# Pico.net
KiCad netlist of a schematic drawn in Altium Designer
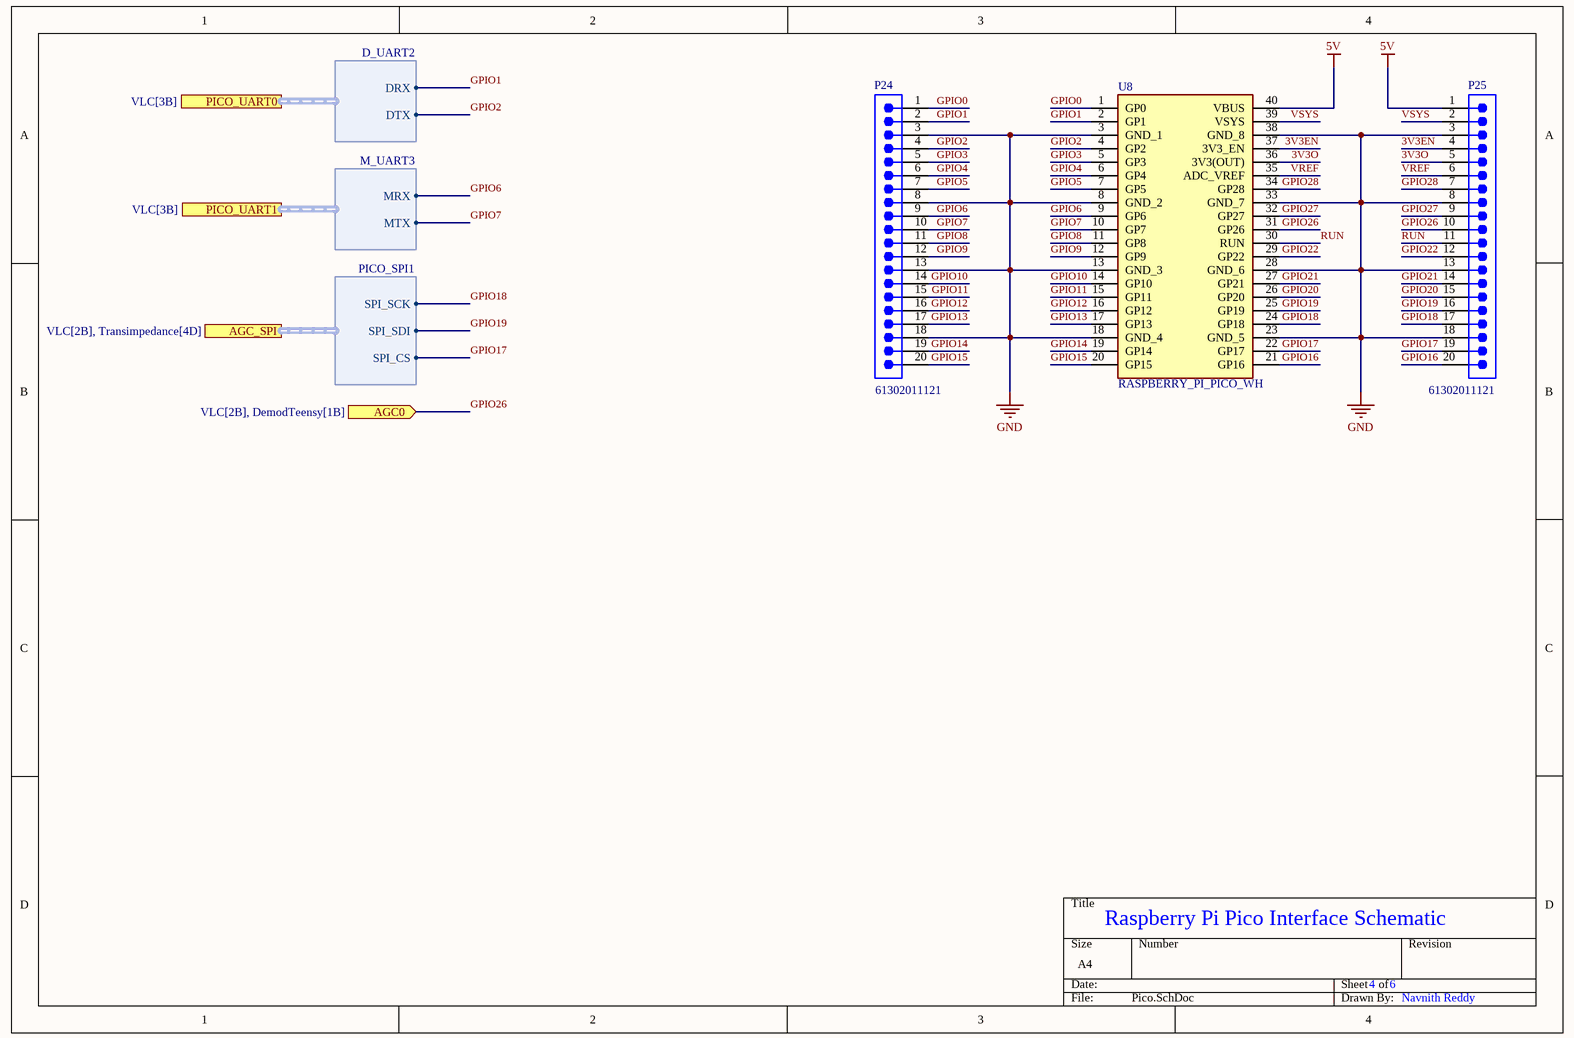
[diagram p0: Pico.SchDoc]

(export (version "E")
  (design (tool "Eeschema 10.0.6"))
  (components
    (comp (ref "P24")
      (value "61302011121")
      (footprint "61302011121")
      (libsource (lib "Altium Content Vault") (part "Header_Male_1R_20P"))
    )
    (comp (ref "P25")
      (value "61302011121")
      (footprint "61302011121")
      (libsource (lib "Altium Content Vault") (part "Header_Male_1R_20P"))
    )
    (comp (ref "U8")
      (value "RASPBERRY_PI_PICO_WH")
      (footprint "SamacSys:RASPBERRYPIPICOWH")
      (description "Undefined or Miscellaneous")
      (fields (field (name "MANUFACTURER_PART_NUMBER") "RASPBERRY PI PICO WH"))
      (libsource (lib "*") (part "RASPBERRY_PI_PICO_WH"))
    )
  )
  (nets
    (net (code "4") (name "/3V3EN") (class "Default")
      (node (ref "P25") (pin "4") (pinfunction "4_4") (pintype "passive"))
      (node (ref "U8") (pin "37") (pinfunction "3V3_EN_37") (pintype "passive"))
    )
    (net (code "5") (name "/3V3O") (class "Default")
      (node (ref "P25") (pin "5") (pinfunction "5_5") (pintype "passive"))
      (node (ref "U8") (pin "36") (pinfunction "3V3(OUT)_36") (pintype "passive"))
    )
    (net (code "6") (name "/GPIO0") (class "Default")
      (node (ref "P24") (pin "1") (pinfunction "1_1") (pintype "passive"))
      (node (ref "U8") (pin "1") (pinfunction "GP0_1") (pintype "passive"))
    )
    (net (code "7") (name "/GPIO1") (class "Default")
      (node (ref "P24") (pin "2") (pinfunction "2_2") (pintype "passive"))
      (node (ref "U8") (pin "2") (pinfunction "GP1_2") (pintype "passive"))
    )
    (net (code "8") (name "/GPIO2") (class "Default")
      (node (ref "P24") (pin "4") (pinfunction "4_4") (pintype "passive"))
      (node (ref "U8") (pin "4") (pinfunction "GP2_4") (pintype "passive"))
    )
    (net (code "9") (name "/GPIO3") (class "Default")
      (node (ref "P24") (pin "5") (pinfunction "5_5") (pintype "passive"))
      (node (ref "U8") (pin "5") (pinfunction "GP3_5") (pintype "passive"))
    )
    (net (code "10") (name "/GPIO4") (class "Default")
      (node (ref "P24") (pin "6") (pinfunction "6_6") (pintype "passive"))
      (node (ref "U8") (pin "6") (pinfunction "GP4_6") (pintype "passive"))
    )
    (net (code "11") (name "/GPIO5") (class "Default")
      (node (ref "P24") (pin "7") (pinfunction "7_7") (pintype "passive"))
      (node (ref "U8") (pin "7") (pinfunction "GP5_7") (pintype "passive"))
    )
    (net (code "12") (name "/GPIO6") (class "Default")
      (node (ref "P24") (pin "9") (pinfunction "9_9") (pintype "passive"))
      (node (ref "U8") (pin "9") (pinfunction "GP6_9") (pintype "passive"))
    )
    (net (code "13") (name "/GPIO7") (class "Default")
      (node (ref "P24") (pin "10") (pinfunction "10_10") (pintype "passive"))
      (node (ref "U8") (pin "10") (pinfunction "GP7_10") (pintype "passive"))
    )
    (net (code "14") (name "/GPIO8") (class "Default")
      (node (ref "P24") (pin "11") (pinfunction "11_11") (pintype "passive"))
      (node (ref "U8") (pin "11") (pinfunction "GP8_11") (pintype "passive"))
    )
    (net (code "15") (name "/GPIO9") (class "Default")
      (node (ref "P24") (pin "12") (pinfunction "12_12") (pintype "passive"))
      (node (ref "U8") (pin "12") (pinfunction "GP9_12") (pintype "passive"))
    )
    (net (code "16") (name "/GPIO10") (class "Default")
      (node (ref "P24") (pin "14") (pinfunction "14_14") (pintype "passive"))
      (node (ref "U8") (pin "14") (pinfunction "GP10_14") (pintype "passive"))
    )
    (net (code "17") (name "/GPIO11") (class "Default")
      (node (ref "P24") (pin "15") (pinfunction "15_15") (pintype "passive"))
      (node (ref "U8") (pin "15") (pinfunction "GP11_15") (pintype "passive"))
    )
    (net (code "18") (name "/GPIO12") (class "Default")
      (node (ref "P24") (pin "16") (pinfunction "16_16") (pintype "passive"))
      (node (ref "U8") (pin "16") (pinfunction "GP12_16") (pintype "passive"))
    )
    (net (code "19") (name "/GPIO13") (class "Default")
      (node (ref "P24") (pin "17") (pinfunction "17_17") (pintype "passive"))
      (node (ref "U8") (pin "17") (pinfunction "GP13_17") (pintype "passive"))
    )
    (net (code "20") (name "/GPIO14") (class "Default")
      (node (ref "P24") (pin "19") (pinfunction "19_19") (pintype "passive"))
      (node (ref "U8") (pin "19") (pinfunction "GP14_19") (pintype "passive"))
    )
    (net (code "21") (name "/GPIO15") (class "Default")
      (node (ref "P24") (pin "20") (pinfunction "20_20") (pintype "passive"))
      (node (ref "U8") (pin "20") (pinfunction "GP15_20") (pintype "passive"))
    )
    (net (code "22") (name "/GPIO16") (class "Default")
      (node (ref "P25") (pin "20") (pinfunction "20_20") (pintype "passive"))
      (node (ref "U8") (pin "21") (pinfunction "GP16_21") (pintype "passive"))
    )
    (net (code "23") (name "/GPIO17") (class "Default")
      (node (ref "P25") (pin "19") (pinfunction "19_19") (pintype "passive"))
      (node (ref "U8") (pin "22") (pinfunction "GP17_22") (pintype "passive"))
    )
    (net (code "24") (name "/GPIO18") (class "Default")
      (node (ref "P25") (pin "17") (pinfunction "17_17") (pintype "passive"))
      (node (ref "U8") (pin "24") (pinfunction "GP18_24") (pintype "passive"))
    )
    (net (code "25") (name "/GPIO19") (class "Default")
      (node (ref "P25") (pin "16") (pinfunction "16_16") (pintype "passive"))
      (node (ref "U8") (pin "25") (pinfunction "GP19_25") (pintype "passive"))
    )
    (net (code "26") (name "/GPIO20") (class "Default")
      (node (ref "P25") (pin "15") (pinfunction "15_15") (pintype "passive"))
      (node (ref "U8") (pin "26") (pinfunction "GP20_26") (pintype "passive"))
    )
    (net (code "27") (name "/GPIO21") (class "Default")
      (node (ref "P25") (pin "14") (pinfunction "14_14") (pintype "passive"))
      (node (ref "U8") (pin "27") (pinfunction "GP21_27") (pintype "passive"))
    )
    (net (code "28") (name "/GPIO22") (class "Default")
      (node (ref "P25") (pin "12") (pinfunction "12_12") (pintype "passive"))
      (node (ref "U8") (pin "29") (pinfunction "GP22_29") (pintype "passive"))
    )
    (net (code "29") (name "/GPIO26") (class "Default")
      (node (ref "P25") (pin "10") (pinfunction "10_10") (pintype "passive"))
      (node (ref "U8") (pin "31") (pinfunction "GP26_31") (pintype "passive"))
    )
    (net (code "30") (name "/GPIO27") (class "Default")
      (node (ref "P25") (pin "9") (pinfunction "9_9") (pintype "passive"))
      (node (ref "U8") (pin "32") (pinfunction "GP27_32") (pintype "passive"))
    )
    (net (code "31") (name "/GPIO28") (class "Default")
      (node (ref "P25") (pin "7") (pinfunction "7_7") (pintype "passive"))
      (node (ref "U8") (pin "34") (pinfunction "GP28_34") (pintype "passive"))
    )
    (net (code "32") (name "/RUN") (class "Default")
      (node (ref "P25") (pin "11") (pinfunction "11_11") (pintype "passive"))
      (node (ref "U8") (pin "30") (pinfunction "RUN_30") (pintype "passive"))
    )
    (net (code "33") (name "/VREF") (class "Default")
      (node (ref "P25") (pin "6") (pinfunction "6_6") (pintype "passive"))
      (node (ref "U8") (pin "35") (pinfunction "ADC_VREF_35") (pintype "passive"))
    )
    (net (code "34") (name "/VSYS") (class "Default")
      (node (ref "P25") (pin "2") (pinfunction "2_2") (pintype "passive"))
      (node (ref "U8") (pin "39") (pinfunction "VSYS_39") (pintype "passive"))
    )
    (net (code "38") (name "5V") (class "Default")
      (node (ref "P25") (pin "1") (pinfunction "1_1") (pintype "passive"))
      (node (ref "U8") (pin "40") (pinfunction "VBUS_40") (pintype "passive"))
    )
    (net (code "39") (name "GND") (class "Default")
      (node (ref "P24") (pin "13") (pinfunction "13_13") (pintype "passive"))
      (node (ref "P24") (pin "18") (pinfunction "18_18") (pintype "passive"))
      (node (ref "P24") (pin "3") (pinfunction "3_3") (pintype "passive"))
      (node (ref "P24") (pin "8") (pinfunction "8_8") (pintype "passive"))
      (node (ref "P25") (pin "13") (pinfunction "13_13") (pintype "passive"))
      (node (ref "P25") (pin "18") (pinfunction "18_18") (pintype "passive"))
      (node (ref "P25") (pin "3") (pinfunction "3_3") (pintype "passive"))
      (node (ref "P25") (pin "8") (pinfunction "8_8") (pintype "passive"))
      (node (ref "U8") (pin "13") (pinfunction "GND_3_13") (pintype "passive"))
      (node (ref "U8") (pin "18") (pinfunction "GND_4_18") (pintype "passive"))
      (node (ref "U8") (pin "23") (pinfunction "GND_5_23") (pintype "passive"))
      (node (ref "U8") (pin "28") (pinfunction "GND_6_28") (pintype "passive"))
      (node (ref "U8") (pin "3") (pinfunction "GND_1_3") (pintype "passive"))
      (node (ref "U8") (pin "33") (pinfunction "GND_7_33") (pintype "passive"))
      (node (ref "U8") (pin "38") (pinfunction "GND_8_38") (pintype "passive"))
      (node (ref "U8") (pin "8") (pinfunction "GND_2_8") (pintype "passive"))
    )
  )
)
